# main.net
KiCad netlist of a schematic drawn in Altium Designer
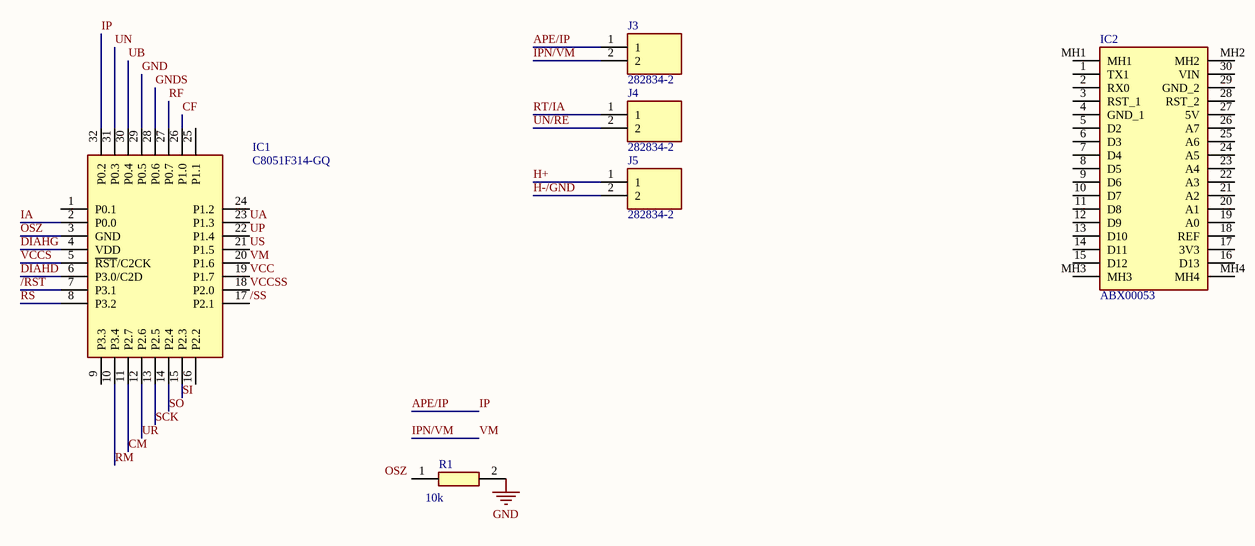
[diagram p0: main.SchDoc]

(export (version "E")
  (design (tool "Eeschema 10.0.6"))
  (components
    (comp (ref "IC1")
      (value "C8051F314-GQ")
      (footprint "SamacSys:QFP80P900X900X160-32N")
      (description "Integrated Circuit")
      (fields (field (name "MOUSER PART NUMBER") "634-C8051F314-GQ"))
      (libsource (lib "*") (part "C8051F314-GQ"))
    )
    (comp (ref "IC2")
      (value "ABX00053")
      (footprint "SamacSys:ABX00053")
      (description "Integrated Circuit")
      (fields (field (name "MOUSER PART NUMBER") "782-ABX00053"))
      (libsource (lib "*") (part "ABX00053"))
    )
    (comp (ref "J3")
      (value "282834-2")
      (footprint "SamacSys:282834-2_1")
      (description "Connector")
      (fields (field (name "MOUSER PART NUMBER") "571-282834-2"))
      (libsource (lib "*") (part "282834-2"))
    )
    (comp (ref "J4")
      (value "282834-2")
      (footprint "SamacSys:282834-2_1")
      (description "Connector")
      (fields (field (name "MOUSER PART NUMBER") "571-282834-2"))
      (libsource (lib "*") (part "282834-2"))
    )
    (comp (ref "J5")
      (value "282834-2")
      (footprint "SamacSys:282834-2_1")
      (description "Connector")
      (fields (field (name "MOUSER PART NUMBER") "571-282834-2"))
      (libsource (lib "*") (part "282834-2"))
    )
    (comp (ref "R1")
      (value "10k")
      (footprint "SamacSys:RESAD1520W63L600D230")
      (description "Resistor")
      (fields
        (field (name "MANUFACTURER_PART_NUMBER") "CF14JT1K00")
        (field (name "MOUSER PART NUMBER") "708-CF14JT1K00")
      )
      (libsource (lib "*") (part "CF14JT1K00"))
    )
  )
  (nets
    (net (code "1") (name "/APE{slash}IP") (class "Default")
      (node (ref "IC1") (pin "32") (pinfunction "P0.2_32") (pintype "passive"))
      (node (ref "J3") (pin "1") (pinfunction "1_1") (pintype "passive"))
    )
    (net (code "2") (name "/CF") (class "Default")
      (node (ref "IC1") (pin "26") (pinfunction "P1.0_26") (pintype "passive"))
    )
    (net (code "3") (name "/CM") (class "Default")
      (node (ref "IC1") (pin "11") (pinfunction "P2.7_11") (pintype "passive"))
    )
    (net (code "4") (name "/DIAHD") (class "Default")
      (node (ref "IC1") (pin "6") (pinfunction "P3.0/C2D_6") (pintype "passive"))
    )
    (net (code "5") (name "/DIAHG") (class "Default")
      (node (ref "IC1") (pin "4") (pinfunction "VDD_4") (pintype "passive"))
    )
    (net (code "6") (name "/GNDS") (class "Default")
      (node (ref "IC1") (pin "28") (pinfunction "P0.6_28") (pintype "passive"))
    )
    (net (code "7") (name "/H+") (class "Default")
      (node (ref "J5") (pin "1") (pinfunction "1_1") (pintype "passive"))
    )
    (net (code "8") (name "/H-{slash}GND") (class "Default")
      (node (ref "J5") (pin "2") (pinfunction "2_2") (pintype "passive"))
    )
    (net (code "9") (name "/IA") (class "Default")
      (node (ref "IC1") (pin "2") (pinfunction "P0.0_2") (pintype "passive"))
    )
    (net (code "10") (name "/IPN{slash}VM") (class "Default")
      (node (ref "IC1") (pin "20") (pinfunction "P1.6_20") (pintype "passive"))
      (node (ref "J3") (pin "2") (pinfunction "2_2") (pintype "passive"))
    )
    (net (code "11") (name "/OSZ") (class "Default")
      (node (ref "IC1") (pin "3") (pinfunction "GND_3") (pintype "passive"))
    )
    (net (code "12") (name "/RF") (class "Default")
      (node (ref "IC1") (pin "27") (pinfunction "P0.7_27") (pintype "passive"))
    )
    (net (code "13") (name "/RM") (class "Default")
      (node (ref "IC1") (pin "10") (pinfunction "P3.4_10") (pintype "passive"))
    )
    (net (code "14") (name "/RS") (class "Default")
      (node (ref "IC1") (pin "8") (pinfunction "P3.2_8") (pintype "passive"))
    )
    (net (code "15") (name "/RT{slash}IA") (class "Default")
      (node (ref "J4") (pin "1") (pinfunction "1_1") (pintype "passive"))
    )
    (net (code "16") (name "/SCK") (class "Default")
      (node (ref "IC1") (pin "13") (pinfunction "P2.5_13") (pintype "passive"))
    )
    (net (code "17") (name "/SI") (class "Default")
      (node (ref "IC1") (pin "15") (pinfunction "P2.3_15") (pintype "passive"))
    )
    (net (code "18") (name "/SO") (class "Default")
      (node (ref "IC1") (pin "14") (pinfunction "P2.4_14") (pintype "passive"))
    )
    (net (code "19") (name "/UA") (class "Default")
      (node (ref "IC1") (pin "23") (pinfunction "P1.3_23") (pintype "passive"))
    )
    (net (code "20") (name "/UB") (class "Default")
      (node (ref "IC1") (pin "30") (pinfunction "P0.4_30") (pintype "passive"))
    )
    (net (code "21") (name "/UN") (class "Default")
      (node (ref "IC1") (pin "31") (pinfunction "P0.3_31") (pintype "passive"))
    )
    (net (code "22") (name "/UN{slash}RE") (class "Default")
      (node (ref "J4") (pin "2") (pinfunction "2_2") (pintype "passive"))
    )
    (net (code "23") (name "/UP") (class "Default")
      (node (ref "IC1") (pin "22") (pinfunction "P1.4_22") (pintype "passive"))
    )
    (net (code "24") (name "/UR") (class "Default")
      (node (ref "IC1") (pin "12") (pinfunction "P2.6_12") (pintype "passive"))
    )
    (net (code "25") (name "/US") (class "Default")
      (node (ref "IC1") (pin "21") (pinfunction "P1.5_21") (pintype "passive"))
    )
    (net (code "26") (name "/VCC") (class "Default")
      (node (ref "IC1") (pin "19") (pinfunction "P1.7_19") (pintype "passive"))
    )
    (net (code "27") (name "/VCCS") (class "Default")
      (node (ref "IC1") (pin "5") (pinfunction "~{RST}/C2CK_5") (pintype "passive"))
    )
    (net (code "28") (name "/VCCSS") (class "Default")
      (node (ref "IC1") (pin "18") (pinfunction "P2.0_18") (pintype "passive"))
    )
    (net (code "29") (name "/{slash}RST") (class "Default")
      (node (ref "IC1") (pin "7") (pinfunction "P3.1_7") (pintype "passive"))
    )
    (net (code "30") (name "/{slash}SS") (class "Default")
      (node (ref "IC1") (pin "17") (pinfunction "P2.1_17") (pintype "passive"))
    )
    (net (code "31") (name "GND") (class "Default")
      (node (ref "IC1") (pin "29") (pinfunction "P0.5_29") (pintype "passive"))
      (node (ref "R1") (pin "2") (pinfunction "2_2") (pintype "passive"))
    )
    (net (code "32") (name "unconnected-(IC1-P0.1-Pad1)") (class "Default")
      (node (ref "IC1") (pin "1") (pinfunction "P0.1_1") (pintype "passive"))
    )
    (net (code "33") (name "unconnected-(IC1-P1.1-Pad25)") (class "Default")
      (node (ref "IC1") (pin "25") (pinfunction "P1.1_25") (pintype "passive"))
    )
    (net (code "34") (name "unconnected-(IC1-P1.2-Pad24)") (class "Default")
      (node (ref "IC1") (pin "24") (pinfunction "P1.2_24") (pintype "passive"))
    )
    (net (code "35") (name "unconnected-(IC1-P2.2-Pad16)") (class "Default")
      (node (ref "IC1") (pin "16") (pinfunction "P2.2_16") (pintype "passive"))
    )
    (net (code "36") (name "unconnected-(IC1-P3.3-Pad9)") (class "Default")
      (node (ref "IC1") (pin "9") (pinfunction "P3.3_9") (pintype "passive"))
    )
    (net (code "37") (name "unconnected-(IC2-3V3-Pad17)") (class "Default")
      (node (ref "IC2") (pin "17") (pinfunction "3V3_17") (pintype "passive"))
    )
    (net (code "38") (name "unconnected-(IC2-5V-Pad27)") (class "Default")
      (node (ref "IC2") (pin "27") (pinfunction "5V_27") (pintype "passive"))
    )
    (net (code "39") (name "unconnected-(IC2-A0-Pad19)") (class "Default")
      (node (ref "IC2") (pin "19") (pinfunction "A0_19") (pintype "passive"))
    )
    (net (code "40") (name "unconnected-(IC2-A1-Pad20)") (class "Default")
      (node (ref "IC2") (pin "20") (pinfunction "A1_20") (pintype "passive"))
    )
    (net (code "41") (name "unconnected-(IC2-A2-Pad21)") (class "Default")
      (node (ref "IC2") (pin "21") (pinfunction "A2_21") (pintype "passive"))
    )
    (net (code "42") (name "unconnected-(IC2-A3-Pad22)") (class "Default")
      (node (ref "IC2") (pin "22") (pinfunction "A3_22") (pintype "passive"))
    )
    (net (code "43") (name "unconnected-(IC2-A4-Pad23)") (class "Default")
      (node (ref "IC2") (pin "23") (pinfunction "A4_23") (pintype "passive"))
    )
    (net (code "44") (name "unconnected-(IC2-A5-Pad24)") (class "Default")
      (node (ref "IC2") (pin "24") (pinfunction "A5_24") (pintype "passive"))
    )
    (net (code "45") (name "unconnected-(IC2-A6-Pad25)") (class "Default")
      (node (ref "IC2") (pin "25") (pinfunction "A6_25") (pintype "passive"))
    )
    (net (code "46") (name "unconnected-(IC2-A7-Pad26)") (class "Default")
      (node (ref "IC2") (pin "26") (pinfunction "A7_26") (pintype "passive"))
    )
    (net (code "47") (name "unconnected-(IC2-D2-Pad5)") (class "Default")
      (node (ref "IC2") (pin "5") (pinfunction "D2_5") (pintype "passive"))
    )
    (net (code "48") (name "unconnected-(IC2-D3-Pad6)") (class "Default")
      (node (ref "IC2") (pin "6") (pinfunction "D3_6") (pintype "passive"))
    )
    (net (code "49") (name "unconnected-(IC2-D4-Pad7)") (class "Default")
      (node (ref "IC2") (pin "7") (pinfunction "D4_7") (pintype "passive"))
    )
    (net (code "50") (name "unconnected-(IC2-D5-Pad8)") (class "Default")
      (node (ref "IC2") (pin "8") (pinfunction "D5_8") (pintype "passive"))
    )
    (net (code "51") (name "unconnected-(IC2-D6-Pad9)") (class "Default")
      (node (ref "IC2") (pin "9") (pinfunction "D6_9") (pintype "passive"))
    )
    (net (code "52") (name "unconnected-(IC2-D7-Pad10)") (class "Default")
      (node (ref "IC2") (pin "10") (pinfunction "D7_10") (pintype "passive"))
    )
    (net (code "53") (name "unconnected-(IC2-D8-Pad11)") (class "Default")
      (node (ref "IC2") (pin "11") (pinfunction "D8_11") (pintype "passive"))
    )
    (net (code "54") (name "unconnected-(IC2-D9-Pad12)") (class "Default")
      (node (ref "IC2") (pin "12") (pinfunction "D9_12") (pintype "passive"))
    )
    (net (code "55") (name "unconnected-(IC2-D10-Pad13)") (class "Default")
      (node (ref "IC2") (pin "13") (pinfunction "D10_13") (pintype "passive"))
    )
    (net (code "56") (name "unconnected-(IC2-D11-Pad14)") (class "Default")
      (node (ref "IC2") (pin "14") (pinfunction "D11_14") (pintype "passive"))
    )
    (net (code "57") (name "unconnected-(IC2-D12-Pad15)") (class "Default")
      (node (ref "IC2") (pin "15") (pinfunction "D12_15") (pintype "passive"))
    )
    (net (code "58") (name "unconnected-(IC2-D13-Pad16)") (class "Default")
      (node (ref "IC2") (pin "16") (pinfunction "D13_16") (pintype "passive"))
    )
    (net (code "59") (name "unconnected-(IC2-GND_1-Pad4)") (class "Default")
      (node (ref "IC2") (pin "4") (pinfunction "GND_1_4") (pintype "passive"))
    )
    (net (code "60") (name "unconnected-(IC2-GND_2-Pad29)") (class "Default")
      (node (ref "IC2") (pin "29") (pinfunction "GND_2_29") (pintype "passive"))
    )
    (net (code "61") (name "unconnected-(IC2-PadMH1)") (class "Default")
      (node (ref "IC2") (pin "MH1") (pinfunction "MH1_MH1") (pintype "passive"))
    )
    (net (code "62") (name "unconnected-(IC2-PadMH2)") (class "Default")
      (node (ref "IC2") (pin "MH2") (pinfunction "MH2_MH2") (pintype "passive"))
    )
    (net (code "63") (name "unconnected-(IC2-PadMH3)") (class "Default")
      (node (ref "IC2") (pin "MH3") (pinfunction "MH3_MH3") (pintype "passive"))
    )
    (net (code "64") (name "unconnected-(IC2-PadMH4)") (class "Default")
      (node (ref "IC2") (pin "MH4") (pinfunction "MH4_MH4") (pintype "passive"))
    )
    (net (code "65") (name "unconnected-(IC2-REF-Pad18)") (class "Default")
      (node (ref "IC2") (pin "18") (pinfunction "REF_18") (pintype "passive"))
    )
    (net (code "66") (name "unconnected-(IC2-RST_1-Pad3)") (class "Default")
      (node (ref "IC2") (pin "3") (pinfunction "RST_1_3") (pintype "passive"))
    )
    (net (code "67") (name "unconnected-(IC2-RST_2-Pad28)") (class "Default")
      (node (ref "IC2") (pin "28") (pinfunction "RST_2_28") (pintype "passive"))
    )
    (net (code "68") (name "unconnected-(IC2-RX0-Pad2)") (class "Default")
      (node (ref "IC2") (pin "2") (pinfunction "RX0_2") (pintype "passive"))
    )
    (net (code "69") (name "unconnected-(IC2-TX1-Pad1)") (class "Default")
      (node (ref "IC2") (pin "1") (pinfunction "TX1_1") (pintype "passive"))
    )
    (net (code "70") (name "unconnected-(IC2-VIN-Pad30)") (class "Default")
      (node (ref "IC2") (pin "30") (pinfunction "VIN_30") (pintype "passive"))
    )
    (net (code "71") (name "unconnected-(R1-Pad1)") (class "Default")
      (node (ref "R1") (pin "1") (pinfunction "1_1") (pintype "passive"))
    )
  )
)
